# shield.net
KiCad netlist of a schematic drawn in EAGLE
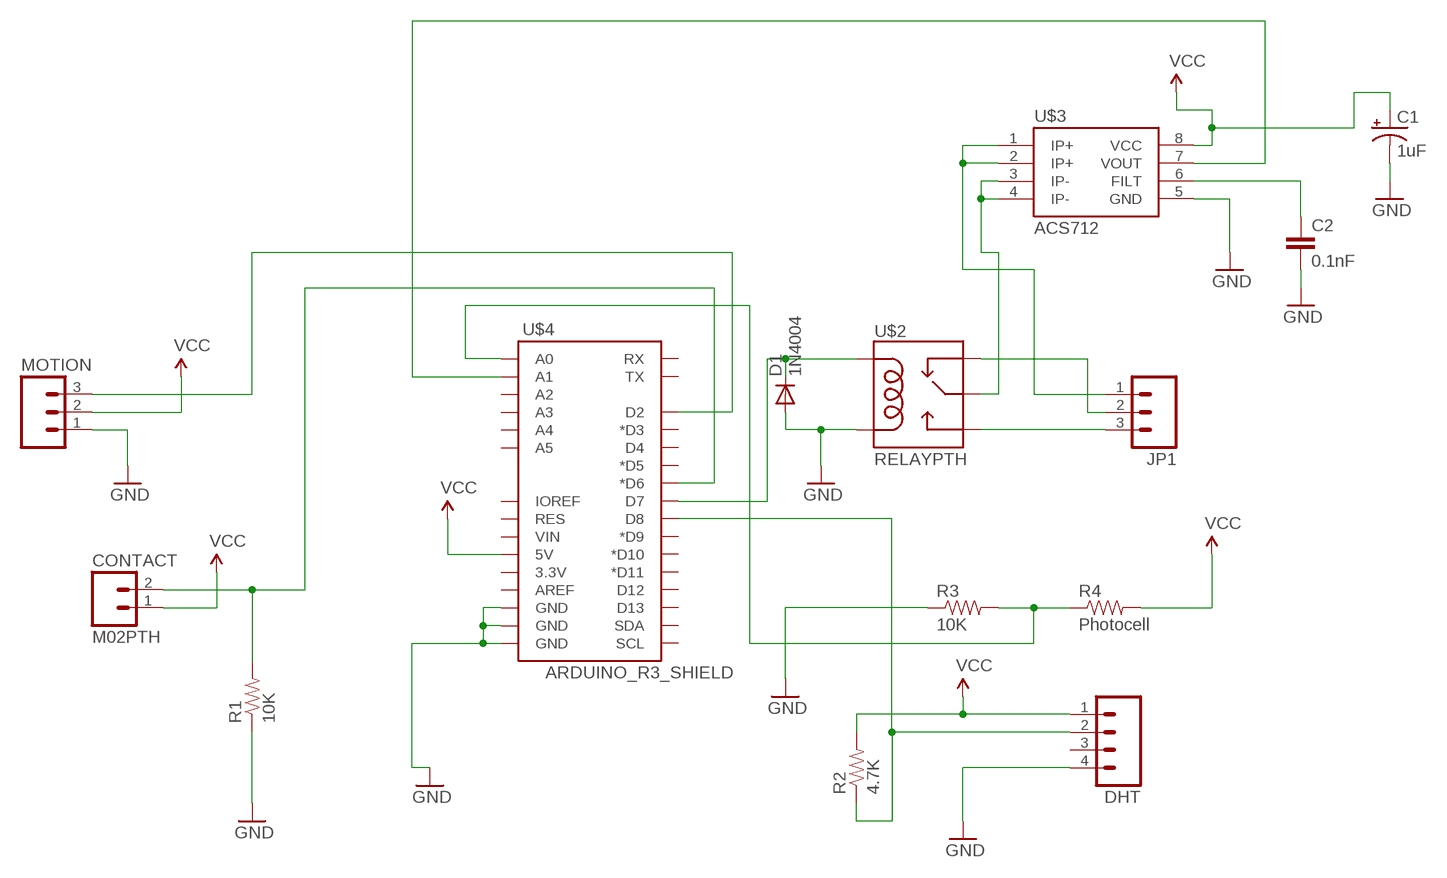
[diagram p0: schematic, sheet 1]

(export (version "E")
  (design (tool "Eeschema 10.0.6"))
  (components
    (comp (ref "C1")
      (value "1uF")
      (footprint "eagle-import:CPOL-RADIAL-10UF-25V")
      (libsource (lib "eagle-import") (part "CAP_POLPTH2"))
    )
    (comp (ref "C2")
      (value "0.1nF")
      (footprint "eagle-import:CAP-PTH-SMALL2")
      (libsource (lib "eagle-import") (part "CAPPTH2"))
    )
    (comp (ref "CONTACT")
      (value "M02PTH")
      (footprint "eagle-import:1X02")
      (libsource (lib "eagle-import") (part "M02PTH"))
    )
    (comp (ref "D1")
      (value "1N4004")
      (footprint "eagle-import:DO41-10")
      (libsource (lib "eagle-import") (part "1N4004"))
    )
    (comp (ref "DHT")
      (value "M04LOCK")
      (footprint "eagle-import:1X04_LOCK")
      (libsource (lib "eagle-import") (part "M04LOCK"))
    )
    (comp (ref "JP1")
      (value "M03SCREW")
      (footprint "eagle-import:SCREWTERMINAL-3.5MM-3")
      (libsource (lib "eagle-import") (part "M03SCREW"))
    )
    (comp (ref "MOTION")
      (value "M03PTH")
      (footprint "eagle-import:1X03")
      (libsource (lib "eagle-import") (part "M03PTH"))
    )
    (comp (ref "R1")
      (value "10K")
      (footprint "eagle-import:AXIAL-0.3")
      (libsource (lib "eagle-import") (part "RESISTORAXIAL-0.3"))
    )
    (comp (ref "R2")
      (value "4.7K")
      (footprint "eagle-import:AXIAL-0.3")
      (libsource (lib "eagle-import") (part "RESISTORAXIAL-0.3"))
    )
    (comp (ref "R3")
      (value "10K")
      (footprint "eagle-import:AXIAL-0.3")
      (libsource (lib "eagle-import") (part "RESISTORAXIAL-0.3"))
    )
    (comp (ref "R4")
      (value "Photocell")
      (footprint "eagle-import:AXIAL-0.3")
      (libsource (lib "eagle-import") (part "RESISTORAXIAL-0.3"))
    )
    (comp (ref "U$2")
      (value "RELAYPTH")
      (footprint "eagle-import:RELAY-G5Q")
      (libsource (lib "eagle-import") (part "RELAYPTH"))
    )
    (comp (ref "U$3")
      (value "ACS712")
      (footprint "eagle-import:SO08")
      (libsource (lib "eagle-import") (part "ACS712"))
    )
    (comp (ref "U$4")
      (value "ARDUINO_R3_SHIELD")
      (footprint "eagle-import:UNO_R3_SHIELD")
      (libsource (lib "eagle-import") (part "ARDUINO_R3_SHIELD"))
    )
  )
  (nets
    (net (code "1") (name "GND") (class "Default")
      (node (ref "C1") (pin "2") (pinfunction "-_2") (pintype "passive"))
      (node (ref "C2") (pin "2") (pinfunction "2_2") (pintype "passive"))
      (node (ref "D1") (pin "A") (pinfunction "A_A") (pintype "passive"))
      (node (ref "DHT") (pin "4") (pinfunction "4_4") (pintype "passive"))
      (node (ref "MOTION") (pin "1") (pinfunction "1_1") (pintype "passive"))
      (node (ref "R1") (pin "P$1") (pinfunction "1_P$1") (pintype "passive"))
      (node (ref "R3") (pin "P$1") (pinfunction "1_P$1") (pintype "passive"))
      (node (ref "U$2") (pin "1") (pinfunction "COIL2_1") (pintype "bidirectional"))
      (node (ref "U$3") (pin "5") (pinfunction "GND_5") (pintype "bidirectional"))
      (node (ref "U$4") (pin "GND@0") (pinfunction "GND_GND@0") (pintype "bidirectional"))
      (node (ref "U$4") (pin "GND@1") (pinfunction "GND_GND@1") (pintype "bidirectional"))
      (node (ref "U$4") (pin "GND@2") (pinfunction "GND_GND@2") (pintype "bidirectional"))
    )
    (net (code "2") (name "Net-(JP1-Pad1)") (class "Default")
      (node (ref "JP1") (pin "1") (pinfunction "1_1") (pintype "passive"))
      (node (ref "U$3") (pin "1") (pinfunction "IP+_1") (pintype "bidirectional"))
      (node (ref "U$3") (pin "2") (pinfunction "IP+_2") (pintype "bidirectional"))
    )
    (net (code "3") (name "Net-(MOTION-Pad3)") (class "Default")
      (node (ref "MOTION") (pin "3") (pinfunction "3_3") (pintype "passive"))
      (node (ref "U$4") (pin "D2") (pinfunction "D2_D2") (pintype "bidirectional"))
    )
    (net (code "4") (name "Net-(R1-2)") (class "Default")
      (node (ref "CONTACT") (pin "2") (pinfunction "2_2") (pintype "passive"))
      (node (ref "R1") (pin "P$2") (pinfunction "2_P$2") (pintype "passive"))
      (node (ref "U$4") (pin "D6") (pinfunction "*D6_D6") (pintype "bidirectional"))
    )
    (net (code "5") (name "Net-(R2-1)") (class "Default")
      (node (ref "DHT") (pin "2") (pinfunction "2_2") (pintype "passive"))
      (node (ref "R2") (pin "P$1") (pinfunction "1_P$1") (pintype "passive"))
      (node (ref "U$4") (pin "D8") (pinfunction "D8_D8") (pintype "bidirectional"))
    )
    (net (code "6") (name "Net-(R3-2)") (class "Default")
      (node (ref "R3") (pin "P$2") (pinfunction "2_P$2") (pintype "passive"))
      (node (ref "R4") (pin "P$1") (pinfunction "1_P$1") (pintype "passive"))
      (node (ref "U$4") (pin "A0") (pinfunction "A0_A0") (pintype "bidirectional"))
    )
    (net (code "7") (name "Net-(U$2-COIL1)") (class "Default")
      (node (ref "D1") (pin "C") (pinfunction "C_C") (pintype "passive"))
      (node (ref "U$2") (pin "5") (pinfunction "COIL1_5") (pintype "bidirectional"))
      (node (ref "U$4") (pin "D7") (pinfunction "D7_D7") (pintype "bidirectional"))
    )
    (net (code "8") (name "Net-(U$2-MAIN)") (class "Default")
      (node (ref "U$2") (pin "2") (pinfunction "MAIN_2") (pintype "bidirectional"))
      (node (ref "U$3") (pin "3") (pinfunction "IP-_3") (pintype "bidirectional"))
      (node (ref "U$3") (pin "4") (pinfunction "IP-_4") (pintype "bidirectional"))
    )
    (net (code "9") (name "Net-(U$2-NC)") (class "Default")
      (node (ref "JP1") (pin "2") (pinfunction "2_2") (pintype "passive"))
      (node (ref "U$2") (pin "4") (pinfunction "NC_4") (pintype "bidirectional"))
    )
    (net (code "10") (name "Net-(U$2-NO)") (class "Default")
      (node (ref "JP1") (pin "3") (pinfunction "3_3") (pintype "passive"))
      (node (ref "U$2") (pin "3") (pinfunction "NO_3") (pintype "bidirectional"))
    )
    (net (code "11") (name "Net-(U$3-FILT)") (class "Default")
      (node (ref "C2") (pin "1") (pinfunction "1_1") (pintype "passive"))
      (node (ref "U$3") (pin "6") (pinfunction "FILT_6") (pintype "bidirectional"))
    )
    (net (code "12") (name "Net-(U$3-VOUT)") (class "Default")
      (node (ref "U$3") (pin "7") (pinfunction "VOUT_7") (pintype "bidirectional"))
      (node (ref "U$4") (pin "A1") (pinfunction "A1_A1") (pintype "bidirectional"))
    )
    (net (code "13") (name "VCC") (class "Default")
      (node (ref "C1") (pin "1") (pinfunction "+_1") (pintype "passive"))
      (node (ref "CONTACT") (pin "1") (pinfunction "1_1") (pintype "passive"))
      (node (ref "DHT") (pin "1") (pinfunction "1_1") (pintype "passive"))
      (node (ref "MOTION") (pin "2") (pinfunction "2_2") (pintype "passive"))
      (node (ref "R2") (pin "P$2") (pinfunction "2_P$2") (pintype "passive"))
      (node (ref "R4") (pin "P$2") (pinfunction "2_P$2") (pintype "passive"))
      (node (ref "U$3") (pin "8") (pinfunction "VCC_8") (pintype "bidirectional"))
      (node (ref "U$4") (pin "5V") (pinfunction "5V_5V") (pintype "bidirectional"))
    )
    (net (code "14") (name "unconnected-(DHT-Pad3)") (class "Default")
      (node (ref "DHT") (pin "3") (pinfunction "3_3") (pintype "passive"))
    )
    (net (code "15") (name "unconnected-(U$4-*D3-PadD3)") (class "Default")
      (node (ref "U$4") (pin "D3") (pinfunction "*D3_D3") (pintype "bidirectional"))
    )
    (net (code "16") (name "unconnected-(U$4-*D5-PadD5)") (class "Default")
      (node (ref "U$4") (pin "D5") (pinfunction "*D5_D5") (pintype "bidirectional"))
    )
    (net (code "17") (name "unconnected-(U$4-*D9-PadD9)") (class "Default")
      (node (ref "U$4") (pin "D9") (pinfunction "*D9_D9") (pintype "bidirectional"))
    )
    (net (code "18") (name "unconnected-(U$4-*D10-PadD10)") (class "Default")
      (node (ref "U$4") (pin "D10") (pinfunction "*D10_D10") (pintype "bidirectional"))
    )
    (net (code "19") (name "unconnected-(U$4-*D11-PadD11)") (class "Default")
      (node (ref "U$4") (pin "D11") (pinfunction "*D11_D11") (pintype "bidirectional"))
    )
    (net (code "20") (name "unconnected-(U$4-Pad3.3V)") (class "Default")
      (node (ref "U$4") (pin "3.3V") (pinfunction "3.3V_3.3V") (pintype "bidirectional"))
    )
    (net (code "21") (name "unconnected-(U$4-PadA2)") (class "Default")
      (node (ref "U$4") (pin "A2") (pinfunction "A2_A2") (pintype "bidirectional"))
    )
    (net (code "22") (name "unconnected-(U$4-PadA3)") (class "Default")
      (node (ref "U$4") (pin "A3") (pinfunction "A3_A3") (pintype "bidirectional"))
    )
    (net (code "23") (name "unconnected-(U$4-PadA4)") (class "Default")
      (node (ref "U$4") (pin "A4") (pinfunction "A4_A4") (pintype "bidirectional"))
    )
    (net (code "24") (name "unconnected-(U$4-PadA5)") (class "Default")
      (node (ref "U$4") (pin "A5") (pinfunction "A5_A5") (pintype "bidirectional"))
    )
    (net (code "25") (name "unconnected-(U$4-PadAREF)") (class "Default")
      (node (ref "U$4") (pin "AREF") (pinfunction "AREF_AREF") (pintype "bidirectional"))
    )
    (net (code "26") (name "unconnected-(U$4-PadD4)") (class "Default")
      (node (ref "U$4") (pin "D4") (pinfunction "D4_D4") (pintype "bidirectional"))
    )
    (net (code "27") (name "unconnected-(U$4-PadD12)") (class "Default")
      (node (ref "U$4") (pin "D12") (pinfunction "D12_D12") (pintype "bidirectional"))
    )
    (net (code "28") (name "unconnected-(U$4-PadD13)") (class "Default")
      (node (ref "U$4") (pin "D13") (pinfunction "D13_D13") (pintype "bidirectional"))
    )
    (net (code "29") (name "unconnected-(U$4-PadIOREF)") (class "Default")
      (node (ref "U$4") (pin "IOREF") (pinfunction "IOREF_IOREF") (pintype "bidirectional"))
    )
    (net (code "30") (name "unconnected-(U$4-PadRES)") (class "Default")
      (node (ref "U$4") (pin "RES") (pinfunction "RES_RES") (pintype "bidirectional"))
    )
    (net (code "31") (name "unconnected-(U$4-PadRX)") (class "Default")
      (node (ref "U$4") (pin "RX") (pinfunction "RX_RX") (pintype "bidirectional"))
    )
    (net (code "32") (name "unconnected-(U$4-PadSCL)") (class "Default")
      (node (ref "U$4") (pin "SCL") (pinfunction "SCL_SCL") (pintype "bidirectional"))
    )
    (net (code "33") (name "unconnected-(U$4-PadSDA)") (class "Default")
      (node (ref "U$4") (pin "SDA") (pinfunction "SDA_SDA") (pintype "bidirectional"))
    )
    (net (code "34") (name "unconnected-(U$4-PadTX)") (class "Default")
      (node (ref "U$4") (pin "TX") (pinfunction "TX_TX") (pintype "bidirectional"))
    )
    (net (code "35") (name "unconnected-(U$4-PadVIN)") (class "Default")
      (node (ref "U$4") (pin "VIN") (pinfunction "VIN_VIN") (pintype "bidirectional"))
    )
  )
)
